# mackenziemillerschem1.net
KiCad netlist of a schematic drawn in Altium Designer
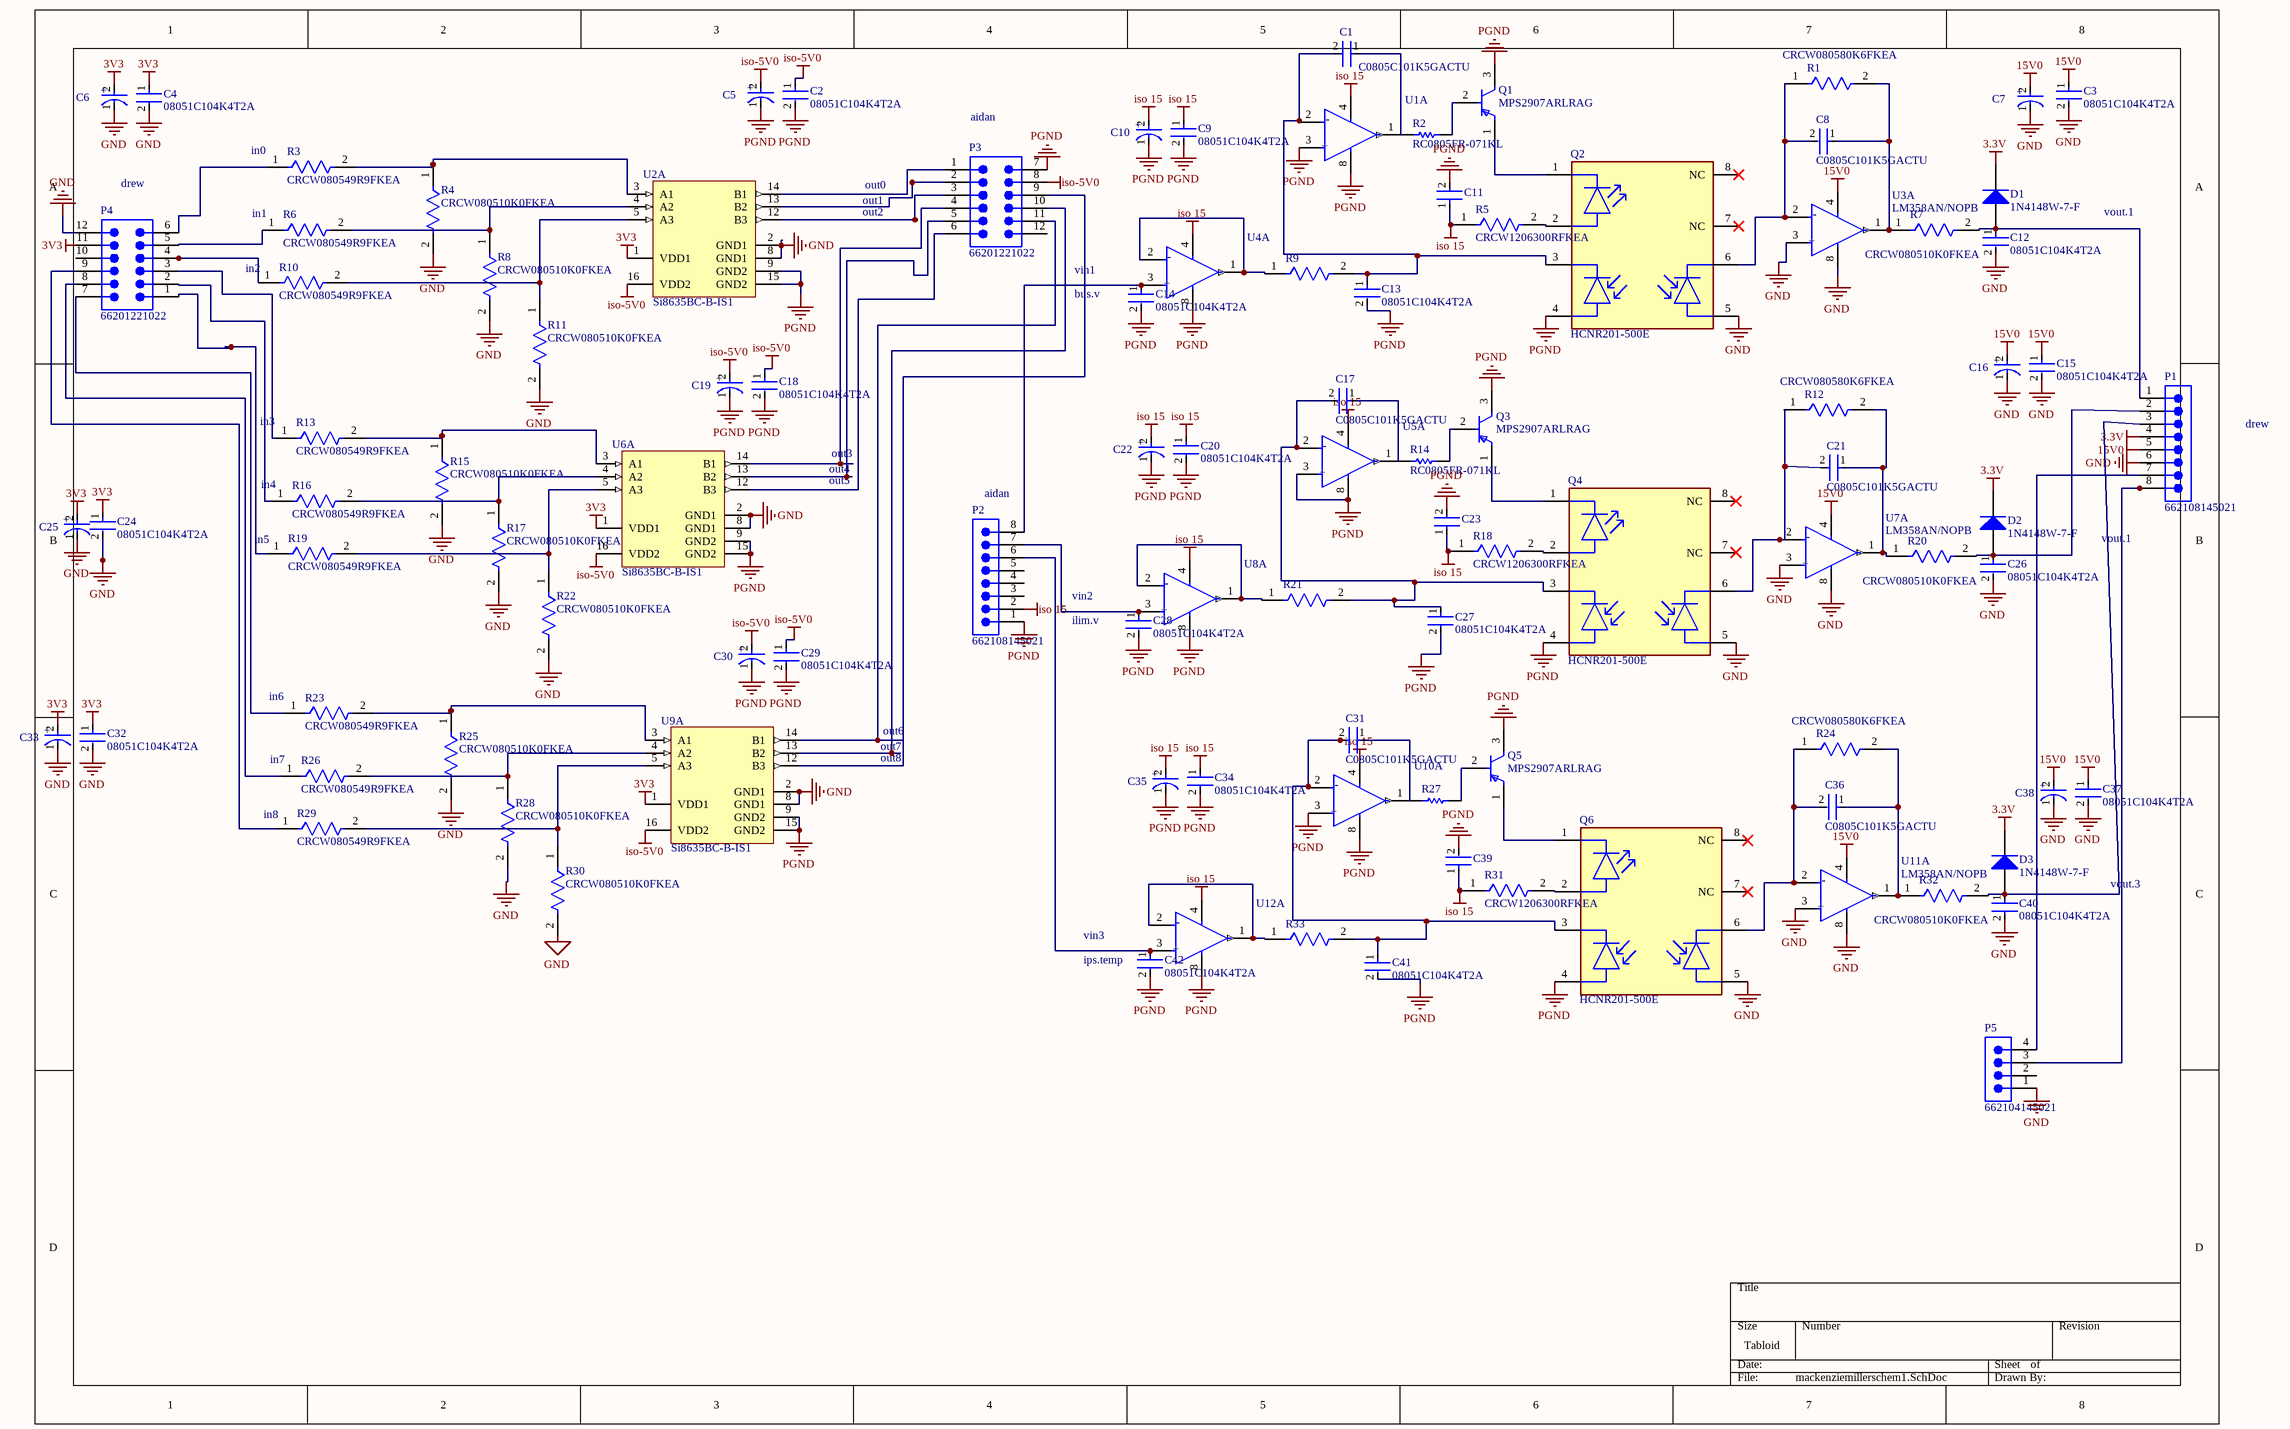
[diagram p0: mackenziemillerschem1.SchDoc]

(export (version "E")
  (design (tool "Eeschema 10.0.6"))
  (components
    (comp (ref "C1")
      (value "C0805C101K5GACTU")
      (footprint "FP-C0805C-DN-MFG")
      (description "CAP CER 100PF 50V C0G/NP0 0805")
      (fields
        (field (name "TOLERANCE") "0.1")
        (field (name "OCTOPART") "https://octopart.com/c0805c101k5gactu-kemet-109877")
      )
      (libsource (lib "Altium Content Vault") (part "b4654b650e69147ec39a6b967a45e02"))
    )
    (comp (ref "C2")
      (value "08051C104K4T2A")
      (footprint "FP-0805-L_2_01_0_2-W_1_25-IPC_B")
      (description "Automotive Ceramic Capacitor, 0805, 100nF, 10%, X7R, 15%, 100V")
      (fields (field (name "TOLERANCE") "10%") (field (name "VOLTAGE") "100V"))
      (libsource (lib "Altium Content Vault") (part "b4654b650e69147ec39a6b967a45e02"))
    )
    (comp (ref "C3")
      (value "08051C104K4T2A")
      (footprint "FP-0805-L_2_01_0_2-W_1_25-IPC_B")
      (description "Automotive Ceramic Capacitor, 0805, 100nF, 10%, X7R, 15%, 100V")
      (fields (field (name "TOLERANCE") "10%") (field (name "VOLTAGE") "100V"))
      (libsource (lib "Altium Content Vault") (part "b4654b650e69147ec39a6b967a45e02"))
    )
    (comp (ref "C4")
      (value "08051C104K4T2A")
      (footprint "FP-0805-L_2_01_0_2-W_1_25-IPC_B")
      (description "Automotive Ceramic Capacitor, 0805, 100nF, 10%, X7R, 15%, 100V")
      (fields (field (name "TOLERANCE") "10%") (field (name "VOLTAGE") "100V"))
      (libsource (lib "Altium Content Vault") (part "b4654b650e69147ec39a6b967a45e02"))
    )
    (comp (ref "C5")
      (value "293D106X9010B2TE3")
      (footprint "FP-293DB-MFG")
      (description "CAP TANT 10UF 10% 10V 1411")
      (fields (field (name "VOLTAGE") "10V") (field (name "TOLERANCE") "10%"))
      (libsource (lib "Altium Content Vault") (part "a00bbbee19879c290e62620ae7e47b1"))
    )
    (comp (ref "C6")
      (value "293D106X9010B2TE3")
      (footprint "FP-293DB-MFG")
      (description "CAP TANT 10UF 10% 10V 1411")
      (fields (field (name "VOLTAGE") "10V") (field (name "TOLERANCE") "10%"))
      (libsource (lib "Altium Content Vault") (part "a00bbbee19879c290e62620ae7e47b1"))
    )
    (comp (ref "C7")
      (value "293D106X9010B2TE3")
      (footprint "FP-293DB-MFG")
      (description "CAP TANT 10UF 10% 10V 1411")
      (fields (field (name "VOLTAGE") "10V") (field (name "TOLERANCE") "10%"))
      (libsource (lib "Altium Content Vault") (part "a00bbbee19879c290e62620ae7e47b1"))
    )
    (comp (ref "C8")
      (value "C0805C101K5GACTU")
      (footprint "FP-C0805C-DN-MFG")
      (description "CAP CER 100PF 50V C0G/NP0 0805")
      (fields
        (field (name "TOLERANCE") "0.1")
        (field (name "OCTOPART") "https://octopart.com/c0805c101k5gactu-kemet-109877")
      )
      (libsource (lib "Altium Content Vault") (part "b4654b650e69147ec39a6b967a45e02"))
    )
    (comp (ref "C9")
      (value "08051C104K4T2A")
      (footprint "FP-0805-L_2_01_0_2-W_1_25-IPC_B")
      (description "Automotive Ceramic Capacitor, 0805, 100nF, 10%, X7R, 15%, 100V")
      (fields (field (name "TOLERANCE") "10%") (field (name "VOLTAGE") "100V"))
      (libsource (lib "Altium Content Vault") (part "b4654b650e69147ec39a6b967a45e02"))
    )
    (comp (ref "C10")
      (value "293D106X9010B2TE3")
      (footprint "FP-293DB-MFG")
      (description "CAP TANT 10UF 10% 10V 1411")
      (fields (field (name "VOLTAGE") "10V") (field (name "TOLERANCE") "10%"))
      (libsource (lib "Altium Content Vault") (part "a00bbbee19879c290e62620ae7e47b1"))
    )
    (comp (ref "C11")
      (value "08051C104K4T2A")
      (footprint "FP-0805-L_2_01_0_2-W_1_25-IPC_B")
      (description "Automotive Ceramic Capacitor, 0805, 100nF, 10%, X7R, 15%, 100V")
      (fields (field (name "TOLERANCE") "10%") (field (name "VOLTAGE") "100V"))
      (libsource (lib "Altium Content Vault") (part "b4654b650e69147ec39a6b967a45e02"))
    )
    (comp (ref "C12")
      (value "08051C104K4T2A")
      (footprint "FP-0805-L_2_01_0_2-W_1_25-IPC_B")
      (description "Automotive Ceramic Capacitor, 0805, 100nF, 10%, X7R, 15%, 100V")
      (fields (field (name "TOLERANCE") "10%") (field (name "VOLTAGE") "100V"))
      (libsource (lib "Altium Content Vault") (part "b4654b650e69147ec39a6b967a45e02"))
    )
    (comp (ref "C13")
      (value "08051C104K4T2A")
      (footprint "FP-0805-L_2_01_0_2-W_1_25-IPC_B")
      (description "Automotive Ceramic Capacitor, 0805, 100nF, 10%, X7R, 15%, 100V")
      (fields (field (name "TOLERANCE") "10%") (field (name "VOLTAGE") "100V"))
      (libsource (lib "Altium Content Vault") (part "b4654b650e69147ec39a6b967a45e02"))
    )
    (comp (ref "C14")
      (value "08051C104K4T2A")
      (footprint "FP-0805-L_2_01_0_2-W_1_25-IPC_B")
      (description "Automotive Ceramic Capacitor, 0805, 100nF, 10%, X7R, 15%, 100V")
      (fields (field (name "TOLERANCE") "10%") (field (name "VOLTAGE") "100V"))
      (libsource (lib "Altium Content Vault") (part "b4654b650e69147ec39a6b967a45e02"))
    )
    (comp (ref "C15")
      (value "08051C104K4T2A")
      (footprint "FP-0805-L_2_01_0_2-W_1_25-IPC_B")
      (description "Automotive Ceramic Capacitor, 0805, 100nF, 10%, X7R, 15%, 100V")
      (fields (field (name "TOLERANCE") "10%") (field (name "VOLTAGE") "100V"))
      (libsource (lib "Altium Content Vault") (part "b4654b650e69147ec39a6b967a45e02"))
    )
    (comp (ref "C16")
      (value "293D106X9010B2TE3")
      (footprint "FP-293DB-MFG")
      (description "CAP TANT 10UF 10% 10V 1411")
      (fields (field (name "VOLTAGE") "10V") (field (name "TOLERANCE") "10%"))
      (libsource (lib "Altium Content Vault") (part "a00bbbee19879c290e62620ae7e47b1"))
    )
    (comp (ref "C17")
      (value "C0805C101K5GACTU")
      (footprint "FP-C0805C-DN-MFG")
      (description "CAP CER 100PF 50V C0G/NP0 0805")
      (fields
        (field (name "TOLERANCE") "0.1")
        (field (name "OCTOPART") "https://octopart.com/c0805c101k5gactu-kemet-109877")
      )
      (libsource (lib "Altium Content Vault") (part "b4654b650e69147ec39a6b967a45e02"))
    )
    (comp (ref "C18")
      (value "08051C104K4T2A")
      (footprint "FP-0805-L_2_01_0_2-W_1_25-IPC_B")
      (description "Automotive Ceramic Capacitor, 0805, 100nF, 10%, X7R, 15%, 100V")
      (fields (field (name "TOLERANCE") "10%") (field (name "VOLTAGE") "100V"))
      (libsource (lib "Altium Content Vault") (part "b4654b650e69147ec39a6b967a45e02"))
    )
    (comp (ref "C19")
      (value "293D106X9010B2TE3")
      (footprint "FP-293DB-MFG")
      (description "CAP TANT 10UF 10% 10V 1411")
      (fields (field (name "VOLTAGE") "10V") (field (name "TOLERANCE") "10%"))
      (libsource (lib "Altium Content Vault") (part "a00bbbee19879c290e62620ae7e47b1"))
    )
    (comp (ref "C20")
      (value "08051C104K4T2A")
      (footprint "FP-0805-L_2_01_0_2-W_1_25-IPC_B")
      (description "Automotive Ceramic Capacitor, 0805, 100nF, 10%, X7R, 15%, 100V")
      (fields (field (name "TOLERANCE") "10%") (field (name "VOLTAGE") "100V"))
      (libsource (lib "Altium Content Vault") (part "b4654b650e69147ec39a6b967a45e02"))
    )
    (comp (ref "C21")
      (value "C0805C101K5GACTU")
      (footprint "FP-C0805C-DN-MFG")
      (description "CAP CER 100PF 50V C0G/NP0 0805")
      (fields
        (field (name "TOLERANCE") "0.1")
        (field (name "OCTOPART") "https://octopart.com/c0805c101k5gactu-kemet-109877")
      )
      (libsource (lib "Altium Content Vault") (part "b4654b650e69147ec39a6b967a45e02"))
    )
    (comp (ref "C22")
      (value "293D106X9010B2TE3")
      (footprint "FP-293DB-MFG")
      (description "CAP TANT 10UF 10% 10V 1411")
      (fields (field (name "VOLTAGE") "10V") (field (name "TOLERANCE") "10%"))
      (libsource (lib "Altium Content Vault") (part "a00bbbee19879c290e62620ae7e47b1"))
    )
    (comp (ref "C23")
      (value "08051C104K4T2A")
      (footprint "FP-0805-L_2_01_0_2-W_1_25-IPC_B")
      (description "Automotive Ceramic Capacitor, 0805, 100nF, 10%, X7R, 15%, 100V")
      (fields (field (name "TOLERANCE") "10%") (field (name "VOLTAGE") "100V"))
      (libsource (lib "Altium Content Vault") (part "b4654b650e69147ec39a6b967a45e02"))
    )
    (comp (ref "C24")
      (value "08051C104K4T2A")
      (footprint "FP-0805-L_2_01_0_2-W_1_25-IPC_B")
      (description "Automotive Ceramic Capacitor, 0805, 100nF, 10%, X7R, 15%, 100V")
      (fields (field (name "TOLERANCE") "10%") (field (name "VOLTAGE") "100V"))
      (libsource (lib "Altium Content Vault") (part "b4654b650e69147ec39a6b967a45e02"))
    )
    (comp (ref "C25")
      (value "293D106X9010B2TE3")
      (footprint "FP-293DB-MFG")
      (description "CAP TANT 10UF 10% 10V 1411")
      (fields (field (name "VOLTAGE") "10V") (field (name "TOLERANCE") "10%"))
      (libsource (lib "Altium Content Vault") (part "a00bbbee19879c290e62620ae7e47b1"))
    )
    (comp (ref "C26")
      (value "08051C104K4T2A")
      (footprint "FP-0805-L_2_01_0_2-W_1_25-IPC_B")
      (description "Automotive Ceramic Capacitor, 0805, 100nF, 10%, X7R, 15%, 100V")
      (fields (field (name "TOLERANCE") "10%") (field (name "VOLTAGE") "100V"))
      (libsource (lib "Altium Content Vault") (part "b4654b650e69147ec39a6b967a45e02"))
    )
    (comp (ref "C27")
      (value "08051C104K4T2A")
      (footprint "FP-0805-L_2_01_0_2-W_1_25-IPC_B")
      (description "Automotive Ceramic Capacitor, 0805, 100nF, 10%, X7R, 15%, 100V")
      (fields (field (name "TOLERANCE") "10%") (field (name "VOLTAGE") "100V"))
      (libsource (lib "Altium Content Vault") (part "b4654b650e69147ec39a6b967a45e02"))
    )
    (comp (ref "C28")
      (value "08051C104K4T2A")
      (footprint "FP-0805-L_2_01_0_2-W_1_25-IPC_B")
      (description "Automotive Ceramic Capacitor, 0805, 100nF, 10%, X7R, 15%, 100V")
      (fields (field (name "TOLERANCE") "10%") (field (name "VOLTAGE") "100V"))
      (libsource (lib "Altium Content Vault") (part "b4654b650e69147ec39a6b967a45e02"))
    )
    (comp (ref "C29")
      (value "08051C104K4T2A")
      (footprint "FP-0805-L_2_01_0_2-W_1_25-IPC_B")
      (description "Automotive Ceramic Capacitor, 0805, 100nF, 10%, X7R, 15%, 100V")
      (fields (field (name "TOLERANCE") "10%") (field (name "VOLTAGE") "100V"))
      (libsource (lib "Altium Content Vault") (part "b4654b650e69147ec39a6b967a45e02"))
    )
    (comp (ref "C30")
      (value "293D106X9010B2TE3")
      (footprint "FP-293DB-MFG")
      (description "CAP TANT 10UF 10% 10V 1411")
      (fields (field (name "VOLTAGE") "10V") (field (name "TOLERANCE") "10%"))
      (libsource (lib "Altium Content Vault") (part "a00bbbee19879c290e62620ae7e47b1"))
    )
    (comp (ref "C31")
      (value "C0805C101K5GACTU")
      (footprint "FP-C0805C-DN-MFG")
      (description "CAP CER 100PF 50V C0G/NP0 0805")
      (fields
        (field (name "TOLERANCE") "0.1")
        (field (name "OCTOPART") "https://octopart.com/c0805c101k5gactu-kemet-109877")
      )
      (libsource (lib "Altium Content Vault") (part "b4654b650e69147ec39a6b967a45e02"))
    )
    (comp (ref "C32")
      (value "08051C104K4T2A")
      (footprint "FP-0805-L_2_01_0_2-W_1_25-IPC_B")
      (description "Automotive Ceramic Capacitor, 0805, 100nF, 10%, X7R, 15%, 100V")
      (fields (field (name "TOLERANCE") "10%") (field (name "VOLTAGE") "100V"))
      (libsource (lib "Altium Content Vault") (part "b4654b650e69147ec39a6b967a45e02"))
    )
    (comp (ref "C33")
      (value "293D106X9010B2TE3")
      (footprint "FP-293DB-MFG")
      (description "CAP TANT 10UF 10% 10V 1411")
      (fields (field (name "VOLTAGE") "10V") (field (name "TOLERANCE") "10%"))
      (libsource (lib "Altium Content Vault") (part "a00bbbee19879c290e62620ae7e47b1"))
    )
    (comp (ref "C34")
      (value "08051C104K4T2A")
      (footprint "FP-0805-L_2_01_0_2-W_1_25-IPC_B")
      (description "Automotive Ceramic Capacitor, 0805, 100nF, 10%, X7R, 15%, 100V")
      (fields (field (name "TOLERANCE") "10%") (field (name "VOLTAGE") "100V"))
      (libsource (lib "Altium Content Vault") (part "b4654b650e69147ec39a6b967a45e02"))
    )
    (comp (ref "C35")
      (value "293D106X9010B2TE3")
      (footprint "FP-293DB-MFG")
      (description "CAP TANT 10UF 10% 10V 1411")
      (fields (field (name "VOLTAGE") "10V") (field (name "TOLERANCE") "10%"))
      (libsource (lib "Altium Content Vault") (part "a00bbbee19879c290e62620ae7e47b1"))
    )
    (comp (ref "C36")
      (value "C0805C101K5GACTU")
      (footprint "FP-C0805C-DN-MFG")
      (description "CAP CER 100PF 50V C0G/NP0 0805")
      (fields
        (field (name "TOLERANCE") "0.1")
        (field (name "OCTOPART") "https://octopart.com/c0805c101k5gactu-kemet-109877")
      )
      (libsource (lib "Altium Content Vault") (part "b4654b650e69147ec39a6b967a45e02"))
    )
    (comp (ref "C37")
      (value "08051C104K4T2A")
      (footprint "FP-0805-L_2_01_0_2-W_1_25-IPC_B")
      (description "Automotive Ceramic Capacitor, 0805, 100nF, 10%, X7R, 15%, 100V")
      (fields (field (name "TOLERANCE") "10%") (field (name "VOLTAGE") "100V"))
      (libsource (lib "Altium Content Vault") (part "b4654b650e69147ec39a6b967a45e02"))
    )
    (comp (ref "C38")
      (value "293D106X9010B2TE3")
      (footprint "FP-293DB-MFG")
      (description "CAP TANT 10UF 10% 10V 1411")
      (fields (field (name "VOLTAGE") "10V") (field (name "TOLERANCE") "10%"))
      (libsource (lib "Altium Content Vault") (part "a00bbbee19879c290e62620ae7e47b1"))
    )
    (comp (ref "C39")
      (value "08051C104K4T2A")
      (footprint "FP-0805-L_2_01_0_2-W_1_25-IPC_B")
      (description "Automotive Ceramic Capacitor, 0805, 100nF, 10%, X7R, 15%, 100V")
      (fields (field (name "TOLERANCE") "10%") (field (name "VOLTAGE") "100V"))
      (libsource (lib "Altium Content Vault") (part "b4654b650e69147ec39a6b967a45e02"))
    )
    (comp (ref "C40")
      (value "08051C104K4T2A")
      (footprint "FP-0805-L_2_01_0_2-W_1_25-IPC_B")
      (description "Automotive Ceramic Capacitor, 0805, 100nF, 10%, X7R, 15%, 100V")
      (fields (field (name "TOLERANCE") "10%") (field (name "VOLTAGE") "100V"))
      (libsource (lib "Altium Content Vault") (part "b4654b650e69147ec39a6b967a45e02"))
    )
    (comp (ref "C41")
      (value "08051C104K4T2A")
      (footprint "FP-0805-L_2_01_0_2-W_1_25-IPC_B")
      (description "Automotive Ceramic Capacitor, 0805, 100nF, 10%, X7R, 15%, 100V")
      (fields (field (name "TOLERANCE") "10%") (field (name "VOLTAGE") "100V"))
      (libsource (lib "Altium Content Vault") (part "b4654b650e69147ec39a6b967a45e02"))
    )
    (comp (ref "C42")
      (value "08051C104K4T2A")
      (footprint "FP-0805-L_2_01_0_2-W_1_25-IPC_B")
      (description "Automotive Ceramic Capacitor, 0805, 100nF, 10%, X7R, 15%, 100V")
      (fields (field (name "TOLERANCE") "10%") (field (name "VOLTAGE") "100V"))
      (libsource (lib "Altium Content Vault") (part "b4654b650e69147ec39a6b967a45e02"))
    )
    (comp (ref "D1")
      (value "1N4148W-7-F")
      (footprint "DIOD-SOD123-2_V")
      (description "Fast Switching Diode, 100 V, 0.15 A, -65 to 150 degC, 2-Pin?SOD123, RoHS, Tape and Reel")
      (fields (field (name "MANUFACTURER") "DiodesIncorporated"))
      (libsource (lib "Altium Content Vault") (part "D-AK-2"))
    )
    (comp (ref "D2")
      (value "1N4148W-7-F")
      (footprint "DIOD-SOD123-2_V")
      (description "Fast Switching Diode, 100 V, 0.15 A, -65 to 150 degC, 2-Pin?SOD123, RoHS, Tape and Reel")
      (fields (field (name "MANUFACTURER") "DiodesIncorporated"))
      (libsource (lib "Altium Content Vault") (part "D-AK-2"))
    )
    (comp (ref "D3")
      (value "1N4148W-7-F")
      (footprint "DIOD-SOD123-2_V")
      (description "Fast Switching Diode, 100 V, 0.15 A, -65 to 150 degC, 2-Pin?SOD123, RoHS, Tape and Reel")
      (fields (field (name "MANUFACTURER") "DiodesIncorporated"))
      (libsource (lib "Altium Content Vault") (part "D-AK-2"))
    )
    (comp (ref "P1")
      (value "662108145021")
      (footprint "662108145021")
      (libsource (lib "Altium Content Vault") (part "Header_Male_1R_08P"))
    )
    (comp (ref "P2")
      (value "662108145021")
      (footprint "662108145021")
      (libsource (lib "Altium Content Vault") (part "Header_Male_1R_08P"))
    )
    (comp (ref "P3")
      (value "66201221022")
      (footprint "66201221022")
      (libsource (lib "Altium Content Vault") (part "Header_Male_2R_12P(A)"))
    )
    (comp (ref "P4")
      (value "66201221022")
      (footprint "66201221022")
      (libsource (lib "Altium Content Vault") (part "Header_Male_2R_12P(A)"))
    )
    (comp (ref "P5")
      (value "662104145021")
      (footprint "662104145021")
      (libsource (lib "Altium Content Vault") (part "Header_Male_1R_04P"))
    )
    (comp (ref "Q1")
      (value "MPS2907ARLRAG")
      (footprint "FP-29-11-MFG")
      (libsource (lib "Altium Content Vault") (part "43163f20067017cd0425b43859cd0db"))
    )
    (comp (ref "Q2")
      (value "HCNR201-500E")
      (footprint "FP-HCNR201-500E-MFG")
      (description "OPTOISO 5KV LINEAR PHVOLT 8DIPGW")
      (libsource (lib "Altium Content Vault") (part "91ab35065b22d0708acdc738a14b8cf"))
    )
    (comp (ref "Q3")
      (value "MPS2907ARLRAG")
      (footprint "FP-29-11-MFG")
      (libsource (lib "Altium Content Vault") (part "43163f20067017cd0425b43859cd0db"))
    )
    (comp (ref "Q4")
      (value "HCNR201-500E")
      (footprint "FP-HCNR201-500E-MFG")
      (description "OPTOISO 5KV LINEAR PHVOLT 8DIPGW")
      (libsource (lib "Altium Content Vault") (part "91ab35065b22d0708acdc738a14b8cf"))
    )
    (comp (ref "Q5")
      (value "MPS2907ARLRAG")
      (footprint "FP-29-11-MFG")
      (libsource (lib "Altium Content Vault") (part "43163f20067017cd0425b43859cd0db"))
    )
    (comp (ref "Q6")
      (value "HCNR201-500E")
      (footprint "FP-HCNR201-500E-MFG")
      (description "OPTOISO 5KV LINEAR PHVOLT 8DIPGW")
      (libsource (lib "Altium Content Vault") (part "91ab35065b22d0708acdc738a14b8cf"))
    )
    (comp (ref "R1")
      (value "CRCW080580K6FKEA")
      (footprint "FP-CRCW0805-e3-IPC_A")
      (description "RES Thick Film, 80.6kΩ, 1%, 0.125W, 100ppm/°C, 0805")
      (fields (field (name "TOLERANCE") "1%"))
      (libsource (lib "Altium Content Vault") (part "1029c3af85768c4190bb7ad29bc67b5"))
    )
    (comp (ref "R2")
      (value "RC0805FR-071KL")
      (footprint "RESC2013X60X35ML10T20")
      (description "Chip Resistor, 1 KOhm, +/- 1%, 125 mW, -55 to 155 degC, 0805 (2012 Metric), RoHS, Tape and Reel")
      (fields (field (name "TOLERANCE") "1%") (field (name "MANUFACTURER") "Yageo"))
      (libsource (lib "Altium Content Vault") (part "RES-2"))
    )
    (comp (ref "R3")
      (value "CRCW080549R9FKEA")
      (footprint "FP-CRCW0805-e3-MFG")
      (description "RES Thick Film, 49.9Ω, 1%, 0.125W, 100ppm/°C, 0805")
      (fields (field (name "TOLERANCE") "1%"))
      (libsource (lib "Altium Content Vault") (part "1029c3af85768c4190bb7ad29bc67b5"))
    )
    (comp (ref "R4")
      (value "CRCW080510K0FKEA")
      (footprint "FP-CRCW0805-e3-IPC_A")
      (description "RES Thick Film, 10kΩ, 1%, 0.125W, 100ppm/°C, 0805")
      (fields (field (name "TOLERANCE") "1%"))
      (libsource (lib "Altium Content Vault") (part "1029c3af85768c4190bb7ad29bc67b5"))
    )
    (comp (ref "R5")
      (value "CRCW1206300RFKEA")
      (footprint "FP-CRCW1206-e3-IPC_A")
      (description "RES Thick Film, 300Ω, 1%, 0.25W, 100ppm/°C, 1206")
      (fields (field (name "TOLERANCE") "1%"))
      (libsource (lib "Altium Content Vault") (part "1029c3af85768c4190bb7ad29bc67b5"))
    )
    (comp (ref "R6")
      (value "CRCW080549R9FKEA")
      (footprint "FP-CRCW0805-e3-MFG")
      (description "RES Thick Film, 49.9Ω, 1%, 0.125W, 100ppm/°C, 0805")
      (fields (field (name "TOLERANCE") "1%"))
      (libsource (lib "Altium Content Vault") (part "1029c3af85768c4190bb7ad29bc67b5"))
    )
    (comp (ref "R7")
      (value "CRCW080510K0FKEA")
      (footprint "FP-CRCW0805-e3-IPC_A")
      (description "RES Thick Film, 10kΩ, 1%, 0.125W, 100ppm/°C, 0805")
      (fields (field (name "TOLERANCE") "1%"))
      (libsource (lib "Altium Content Vault") (part "1029c3af85768c4190bb7ad29bc67b5"))
    )
    (comp (ref "R8")
      (value "CRCW080510K0FKEA")
      (footprint "FP-CRCW0805-e3-IPC_A")
      (description "RES Thick Film, 10kΩ, 1%, 0.125W, 100ppm/°C, 0805")
      (fields (field (name "TOLERANCE") "1%"))
      (libsource (lib "Altium Content Vault") (part "1029c3af85768c4190bb7ad29bc67b5"))
    )
    (comp (ref "R9")
      (value "CRCW080580K6FKEA")
      (footprint "FP-CRCW0805-e3-IPC_A")
      (description "RES Thick Film, 80.6kΩ, 1%, 0.125W, 100ppm/°C, 0805")
      (fields (field (name "TOLERANCE") "1%"))
      (libsource (lib "Altium Content Vault") (part "1029c3af85768c4190bb7ad29bc67b5"))
    )
    (comp (ref "R10")
      (value "CRCW080549R9FKEA")
      (footprint "FP-CRCW0805-e3-MFG")
      (description "RES Thick Film, 49.9Ω, 1%, 0.125W, 100ppm/°C, 0805")
      (fields (field (name "TOLERANCE") "1%"))
      (libsource (lib "Altium Content Vault") (part "1029c3af85768c4190bb7ad29bc67b5"))
    )
    (comp (ref "R11")
      (value "CRCW080510K0FKEA")
      (footprint "FP-CRCW0805-e3-IPC_A")
      (description "RES Thick Film, 10kΩ, 1%, 0.125W, 100ppm/°C, 0805")
      (fields (field (name "TOLERANCE") "1%"))
      (libsource (lib "Altium Content Vault") (part "1029c3af85768c4190bb7ad29bc67b5"))
    )
    (comp (ref "R12")
      (value "CRCW080580K6FKEA")
      (footprint "FP-CRCW0805-e3-IPC_A")
      (description "RES Thick Film, 80.6kΩ, 1%, 0.125W, 100ppm/°C, 0805")
      (fields (field (name "TOLERANCE") "1%"))
      (libsource (lib "Altium Content Vault") (part "1029c3af85768c4190bb7ad29bc67b5"))
    )
    (comp (ref "R13")
      (value "CRCW080549R9FKEA")
      (footprint "FP-CRCW0805-e3-MFG")
      (description "RES Thick Film, 49.9Ω, 1%, 0.125W, 100ppm/°C, 0805")
      (fields (field (name "TOLERANCE") "1%"))
      (libsource (lib "Altium Content Vault") (part "1029c3af85768c4190bb7ad29bc67b5"))
    )
    (comp (ref "R14")
      (value "RC0805FR-071KL")
      (footprint "RESC2013X60X35ML10T20")
      (description "Chip Resistor, 1 KOhm, +/- 1%, 125 mW, -55 to 155 degC, 0805 (2012 Metric), RoHS, Tape and Reel")
      (fields (field (name "TOLERANCE") "1%") (field (name "MANUFACTURER") "Yageo"))
      (libsource (lib "Altium Content Vault") (part "RES-2"))
    )
    (comp (ref "R15")
      (value "CRCW080510K0FKEA")
      (footprint "FP-CRCW0805-e3-IPC_A")
      (description "RES Thick Film, 10kΩ, 1%, 0.125W, 100ppm/°C, 0805")
      (fields (field (name "TOLERANCE") "1%"))
      (libsource (lib "Altium Content Vault") (part "1029c3af85768c4190bb7ad29bc67b5"))
    )
    (comp (ref "R16")
      (value "CRCW080549R9FKEA")
      (footprint "FP-CRCW0805-e3-MFG")
      (description "RES Thick Film, 49.9Ω, 1%, 0.125W, 100ppm/°C, 0805")
      (fields (field (name "TOLERANCE") "1%"))
      (libsource (lib "Altium Content Vault") (part "1029c3af85768c4190bb7ad29bc67b5"))
    )
    (comp (ref "R17")
      (value "CRCW080510K0FKEA")
      (footprint "FP-CRCW0805-e3-IPC_A")
      (description "RES Thick Film, 10kΩ, 1%, 0.125W, 100ppm/°C, 0805")
      (fields (field (name "TOLERANCE") "1%"))
      (libsource (lib "Altium Content Vault") (part "1029c3af85768c4190bb7ad29bc67b5"))
    )
    (comp (ref "R18")
      (value "CRCW1206300RFKEA")
      (footprint "FP-CRCW1206-e3-IPC_A")
      (description "RES Thick Film, 300Ω, 1%, 0.25W, 100ppm/°C, 1206")
      (fields (field (name "TOLERANCE") "1%"))
      (libsource (lib "Altium Content Vault") (part "1029c3af85768c4190bb7ad29bc67b5"))
    )
    (comp (ref "R19")
      (value "CRCW080549R9FKEA")
      (footprint "FP-CRCW0805-e3-MFG")
      (description "RES Thick Film, 49.9Ω, 1%, 0.125W, 100ppm/°C, 0805")
      (fields (field (name "TOLERANCE") "1%"))
      (libsource (lib "Altium Content Vault") (part "1029c3af85768c4190bb7ad29bc67b5"))
    )
    (comp (ref "R20")
      (value "CRCW080510K0FKEA")
      (footprint "FP-CRCW0805-e3-IPC_A")
      (description "RES Thick Film, 10kΩ, 1%, 0.125W, 100ppm/°C, 0805")
      (fields (field (name "TOLERANCE") "1%"))
      (libsource (lib "Altium Content Vault") (part "1029c3af85768c4190bb7ad29bc67b5"))
    )
    (comp (ref "R21")
      (value "CRCW080580K6FKEA")
      (footprint "FP-CRCW0805-e3-IPC_A")
      (description "RES Thick Film, 80.6kΩ, 1%, 0.125W, 100ppm/°C, 0805")
      (fields (field (name "TOLERANCE") "1%"))
      (libsource (lib "Altium Content Vault") (part "1029c3af85768c4190bb7ad29bc67b5"))
    )
    (comp (ref "R22")
      (value "CRCW080510K0FKEA")
      (footprint "FP-CRCW0805-e3-IPC_A")
      (description "RES Thick Film, 10kΩ, 1%, 0.125W, 100ppm/°C, 0805")
      (fields (field (name "TOLERANCE") "1%"))
      (libsource (lib "Altium Content Vault") (part "1029c3af85768c4190bb7ad29bc67b5"))
    )
    (comp (ref "R23")
      (value "CRCW080549R9FKEA")
      (footprint "FP-CRCW0805-e3-MFG")
      (description "RES Thick Film, 49.9Ω, 1%, 0.125W, 100ppm/°C, 0805")
      (fields (field (name "TOLERANCE") "1%"))
      (libsource (lib "Altium Content Vault") (part "1029c3af85768c4190bb7ad29bc67b5"))
    )
    (comp (ref "R24")
      (value "CRCW080580K6FKEA")
      (footprint "FP-CRCW0805-e3-IPC_A")
      (description "RES Thick Film, 80.6kΩ, 1%, 0.125W, 100ppm/°C, 0805")
      (fields (field (name "TOLERANCE") "1%"))
      (libsource (lib "Altium Content Vault") (part "1029c3af85768c4190bb7ad29bc67b5"))
    )
    (comp (ref "R25")
      (value "CRCW080510K0FKEA")
      (footprint "FP-CRCW0805-e3-IPC_A")
      (description "RES Thick Film, 10kΩ, 1%, 0.125W, 100ppm/°C, 0805")
      (fields (field (name "TOLERANCE") "1%"))
      (libsource (lib "Altium Content Vault") (part "1029c3af85768c4190bb7ad29bc67b5"))
    )
    (comp (ref "R26")
      (value "CRCW080549R9FKEA")
      (footprint "FP-CRCW0805-e3-MFG")
      (description "RES Thick Film, 49.9Ω, 1%, 0.125W, 100ppm/°C, 0805")
      (fields (field (name "TOLERANCE") "1%"))
      (libsource (lib "Altium Content Vault") (part "1029c3af85768c4190bb7ad29bc67b5"))
    )
    (comp (ref "R27")
      (value "RC0805FR-071KL")
      (footprint "RESC2013X60X35ML10T20")
      (description "Chip Resistor, 1 KOhm, +/- 1%, 125 mW, -55 to 155 degC, 0805 (2012 Metric), RoHS, Tape and Reel")
      (fields (field (name "TOLERANCE") "1%") (field (name "MANUFACTURER") "Yageo"))
      (libsource (lib "Altium Content Vault") (part "RES-2"))
    )
    (comp (ref "R28")
      (value "CRCW080510K0FKEA")
      (footprint "FP-CRCW0805-e3-IPC_A")
      (description "RES Thick Film, 10kΩ, 1%, 0.125W, 100ppm/°C, 0805")
      (fields (field (name "TOLERANCE") "1%"))
      (libsource (lib "Altium Content Vault") (part "1029c3af85768c4190bb7ad29bc67b5"))
    )
    (comp (ref "R29")
      (value "CRCW080549R9FKEA")
      (footprint "FP-CRCW0805-e3-MFG")
      (description "RES Thick Film, 49.9Ω, 1%, 0.125W, 100ppm/°C, 0805")
      (fields (field (name "TOLERANCE") "1%"))
      (libsource (lib "Altium Content Vault") (part "1029c3af85768c4190bb7ad29bc67b5"))
    )
    (comp (ref "R30")
      (value "CRCW080510K0FKEA")
      (footprint "FP-CRCW0805-e3-IPC_A")
      (description "RES Thick Film, 10kΩ, 1%, 0.125W, 100ppm/°C, 0805")
      (fields (field (name "TOLERANCE") "1%"))
      (libsource (lib "Altium Content Vault") (part "1029c3af85768c4190bb7ad29bc67b5"))
    )
    (comp (ref "R31")
      (value "CRCW1206300RFKEA")
      (footprint "FP-CRCW1206-e3-IPC_A")
      (description "RES Thick Film, 300Ω, 1%, 0.25W, 100ppm/°C, 1206")
      (fields (field (name "TOLERANCE") "1%"))
      (libsource (lib "Altium Content Vault") (part "1029c3af85768c4190bb7ad29bc67b5"))
    )
    (comp (ref "R32")
      (value "CRCW080510K0FKEA")
      (footprint "FP-CRCW0805-e3-IPC_A")
      (description "RES Thick Film, 10kΩ, 1%, 0.125W, 100ppm/°C, 0805")
      (fields (field (name "TOLERANCE") "1%"))
      (libsource (lib "Altium Content Vault") (part "1029c3af85768c4190bb7ad29bc67b5"))
    )
    (comp (ref "R33")
      (value "CRCW080580K6FKEA")
      (footprint "FP-CRCW0805-e3-IPC_A")
      (description "RES Thick Film, 80.6kΩ, 1%, 0.125W, 100ppm/°C, 0805")
      (fields (field (name "TOLERANCE") "1%"))
      (libsource (lib "Altium Content Vault") (part "1029c3af85768c4190bb7ad29bc67b5"))
    )
    (comp (ref "U1")
      (value "LM358AN/NOPB")
      (footprint "FP-P0008A-MFG")
      (description "IC OPAMP GP 2 CIRCUIT 8DIP")
      (fields
        (field (name "MANUFACTURER") "Texas Instruments")
        (field (name "OCTOPART") "https://octopart.com/lm358an%2Fnopb-texas+instruments-24814014")
      )
      (libsource (lib "Altium Content Vault") (part "1d8c551adc971fa6d54955cbfc8f220"))
    )
    (comp (ref "U2")
      (value "Si8635BC-B-IS1")
      (footprint "SLAB-SOIC-16-NB_L")
      (fields (field (name "MANUFACTURER") "Silicon Labs"))
      (libsource (lib "Altium Content Vault") (part "SLAB-Si8435BB-SOIC-16-XB-16"))
    )
    (comp (ref "U3")
      (value "LM358AN/NOPB")
      (footprint "FP-P0008A-MFG")
      (description "IC OPAMP GP 2 CIRCUIT 8DIP")
      (fields
        (field (name "MANUFACTURER") "Texas Instruments")
        (field (name "OCTOPART") "https://octopart.com/lm358an%2Fnopb-texas+instruments-24814014")
      )
      (libsource (lib "Altium Content Vault") (part "1d8c551adc971fa6d54955cbfc8f220"))
    )
    (comp (ref "U4")
      (value "LM358AN/NOPB")
      (footprint "FP-P0008A-MFG")
      (description "IC OPAMP GP 2 CIRCUIT 8DIP")
      (fields
        (field (name "MANUFACTURER") "Texas Instruments")
        (field (name "OCTOPART") "https://octopart.com/lm358an%2Fnopb-texas+instruments-24814014")
      )
      (libsource (lib "Altium Content Vault") (part "1d8c551adc971fa6d54955cbfc8f220"))
    )
    (comp (ref "U5")
      (value "LM358AN/NOPB")
      (footprint "FP-P0008A-MFG")
      (description "IC OPAMP GP 2 CIRCUIT 8DIP")
      (fields
        (field (name "MANUFACTURER") "Texas Instruments")
        (field (name "OCTOPART") "https://octopart.com/lm358an%2Fnopb-texas+instruments-24814014")
      )
      (libsource (lib "Altium Content Vault") (part "1d8c551adc971fa6d54955cbfc8f220"))
    )
    (comp (ref "U6")
      (value "Si8635BC-B-IS1")
      (footprint "SLAB-SOIC-16-NB_L")
      (fields (field (name "MANUFACTURER") "Silicon Labs"))
      (libsource (lib "Altium Content Vault") (part "SLAB-Si8435BB-SOIC-16-XB-16"))
    )
    (comp (ref "U7")
      (value "LM358AN/NOPB")
      (footprint "FP-P0008A-MFG")
      (description "IC OPAMP GP 2 CIRCUIT 8DIP")
      (fields
        (field (name "MANUFACTURER") "Texas Instruments")
        (field (name "OCTOPART") "https://octopart.com/lm358an%2Fnopb-texas+instruments-24814014")
      )
      (libsource (lib "Altium Content Vault") (part "1d8c551adc971fa6d54955cbfc8f220"))
    )
    (comp (ref "U8")
      (value "LM358AN/NOPB")
      (footprint "FP-P0008A-MFG")
      (description "IC OPAMP GP 2 CIRCUIT 8DIP")
      (fields
        (field (name "MANUFACTURER") "Texas Instruments")
        (field (name "OCTOPART") "https://octopart.com/lm358an%2Fnopb-texas+instruments-24814014")
      )
      (libsource (lib "Altium Content Vault") (part "1d8c551adc971fa6d54955cbfc8f220"))
    )
    (comp (ref "U9")
      (value "Si8635BC-B-IS1")
      (footprint "SLAB-SOIC-16-NB_L")
      (fields (field (name "MANUFACTURER") "Silicon Labs"))
      (libsource (lib "Altium Content Vault") (part "SLAB-Si8435BB-SOIC-16-XB-16"))
    )
    (comp (ref "U10")
      (value "LM358AN/NOPB")
      (footprint "FP-P0008A-MFG")
      (description "IC OPAMP GP 2 CIRCUIT 8DIP")
      (fields
        (field (name "MANUFACTURER") "Texas Instruments")
        (field (name "OCTOPART") "https://octopart.com/lm358an%2Fnopb-texas+instruments-24814014")
      )
      (libsource (lib "Altium Content Vault") (part "1d8c551adc971fa6d54955cbfc8f220"))
    )
    (comp (ref "U11")
      (value "LM358AN/NOPB")
      (footprint "FP-P0008A-MFG")
      (description "IC OPAMP GP 2 CIRCUIT 8DIP")
      (fields
        (field (name "MANUFACTURER") "Texas Instruments")
        (field (name "OCTOPART") "https://octopart.com/lm358an%2Fnopb-texas+instruments-24814014")
      )
      (libsource (lib "Altium Content Vault") (part "1d8c551adc971fa6d54955cbfc8f220"))
    )
    (comp (ref "U12")
      (value "LM358AN/NOPB")
      (footprint "FP-P0008A-MFG")
      (description "IC OPAMP GP 2 CIRCUIT 8DIP")
      (fields
        (field (name "MANUFACTURER") "Texas Instruments")
        (field (name "OCTOPART") "https://octopart.com/lm358an%2Fnopb-texas+instruments-24814014")
      )
      (libsource (lib "Altium Content Vault") (part "1d8c551adc971fa6d54955cbfc8f220"))
    )
  )
  (nets
    (net (code "1") (name "3.3V") (class "Default")
      (node (ref "D1") (pin "2") (pinfunction "K_2") (pintype "passive"))
      (node (ref "D2") (pin "2") (pinfunction "K_2") (pintype "passive"))
      (node (ref "D3") (pin "2") (pinfunction "K_2") (pintype "passive"))
      (node (ref "P1") (pin "4") (pinfunction "4_4") (pintype "passive"))
    )
    (net (code "2") (name "3V3") (class "Default")
      (node (ref "C24") (pin "1") (pinfunction "1_1") (pintype "passive"))
      (node (ref "C25") (pin "2") (pinfunction "A_2") (pintype "passive"))
      (node (ref "C32") (pin "1") (pinfunction "1_1") (pintype "passive"))
      (node (ref "C33") (pin "2") (pinfunction "A_2") (pintype "passive"))
      (node (ref "C4") (pin "1") (pinfunction "1_1") (pintype "passive"))
      (node (ref "C6") (pin "2") (pinfunction "A_2") (pintype "passive"))
      (node (ref "U2") (pin "1") (pinfunction "VDD1_1") (pintype "power_in"))
      (node (ref "U6") (pin "1") (pinfunction "VDD1_1") (pintype "power_in"))
      (node (ref "U9") (pin "1") (pinfunction "VDD1_1") (pintype "power_in"))
    )
    (net (code "3") (name "15V0") (class "Default")
      (node (ref "C15") (pin "1") (pinfunction "1_1") (pintype "passive"))
      (node (ref "C16") (pin "2") (pinfunction "A_2") (pintype "passive"))
      (node (ref "C3") (pin "1") (pinfunction "1_1") (pintype "passive"))
      (node (ref "C37") (pin "1") (pinfunction "1_1") (pintype "passive"))
      (node (ref "C38") (pin "2") (pinfunction "A_2") (pintype "passive"))
      (node (ref "C7") (pin "2") (pinfunction "A_2") (pintype "passive"))
      (node (ref "P1") (pin "5") (pinfunction "5_5") (pintype "passive"))
      (node (ref "U11") (pin "4") (pinfunction "GND_4") (pintype "power_in"))
      (node (ref "U3") (pin "4") (pinfunction "GND_4") (pintype "power_in"))
      (node (ref "U7") (pin "4") (pinfunction "GND_4") (pintype "power_in"))
    )
    (net (code "4") (name "GND") (class "Default")
      (node (ref "C12") (pin "2") (pinfunction "2_2") (pintype "passive"))
      (node (ref "C15") (pin "2") (pinfunction "2_2") (pintype "passive"))
      (node (ref "C16") (pin "1") (pinfunction "C_1") (pintype "passive"))
      (node (ref "C24") (pin "2") (pinfunction "2_2") (pintype "passive"))
      (node (ref "C25") (pin "1") (pinfunction "C_1") (pintype "passive"))
      (node (ref "C26") (pin "2") (pinfunction "2_2") (pintype "passive"))
      (node (ref "C3") (pin "2") (pinfunction "2_2") (pintype "passive"))
      (node (ref "C32") (pin "2") (pinfunction "2_2") (pintype "passive"))
      (node (ref "C33") (pin "1") (pinfunction "C_1") (pintype "passive"))
      (node (ref "C37") (pin "2") (pinfunction "2_2") (pintype "passive"))
      (node (ref "C38") (pin "1") (pinfunction "C_1") (pintype "passive"))
      (node (ref "C4") (pin "2") (pinfunction "2_2") (pintype "passive"))
      (node (ref "C40") (pin "2") (pinfunction "2_2") (pintype "passive"))
      (node (ref "C6") (pin "1") (pinfunction "C_1") (pintype "passive"))
      (node (ref "C7") (pin "1") (pinfunction "C_1") (pintype "passive"))
      (node (ref "P1") (pin "6") (pinfunction "6_6") (pintype "passive"))
      (node (ref "P4") (pin "12") (pinfunction "12_12") (pintype "passive"))
      (node (ref "P5") (pin "1") (pinfunction "1_1") (pintype "passive"))
      (node (ref "Q2") (pin "5") (pinfunction "PD2_ANODE_5") (pintype "passive"))
      (node (ref "Q4") (pin "5") (pinfunction "PD2_ANODE_5") (pintype "passive"))
      (node (ref "Q6") (pin "5") (pinfunction "PD2_ANODE_5") (pintype "passive"))
      (node (ref "R11") (pin "2") (pinfunction "2_2") (pintype "passive"))
      (node (ref "R15") (pin "2") (pinfunction "2_2") (pintype "passive"))
      (node (ref "R17") (pin "2") (pinfunction "2_2") (pintype "passive"))
      (node (ref "R22") (pin "2") (pinfunction "2_2") (pintype "passive"))
      (node (ref "R25") (pin "2") (pinfunction "2_2") (pintype "passive"))
      (node (ref "R28") (pin "2") (pinfunction "2_2") (pintype "passive"))
      (node (ref "R30") (pin "2") (pinfunction "2_2") (pintype "passive"))
      (node (ref "R4") (pin "2") (pinfunction "2_2") (pintype "passive"))
      (node (ref "R8") (pin "2") (pinfunction "2_2") (pintype "passive"))
      (node (ref "U11") (pin "3") (pinfunction "NON-INVERTING_INPUT_A_3") (pintype "tri_state"))
      (node (ref "U11") (pin "8") (pinfunction "V+_8") (pintype "power_in"))
      (node (ref "U2") (pin "2") (pinfunction "GND1_2") (pintype "power_in"))
      (node (ref "U2") (pin "8") (pinfunction "GND1_8") (pintype "power_in"))
      (node (ref "U3") (pin "3") (pinfunction "NON-INVERTING_INPUT_A_3") (pintype "tri_state"))
      (node (ref "U3") (pin "8") (pinfunction "V+_8") (pintype "power_in"))
      (node (ref "U6") (pin "2") (pinfunction "GND1_2") (pintype "power_in"))
      (node (ref "U6") (pin "8") (pinfunction "GND1_8") (pintype "power_in"))
      (node (ref "U7") (pin "3") (pinfunction "NON-INVERTING_INPUT_A_3") (pintype "tri_state"))
      (node (ref "U7") (pin "8") (pinfunction "V+_8") (pintype "power_in"))
      (node (ref "U9") (pin "2") (pinfunction "GND1_2") (pintype "power_in"))
      (node (ref "U9") (pin "8") (pinfunction "GND1_8") (pintype "power_in"))
    )
    (net (code "5") (name "Net-(C1-Pad1)") (class "Default")
      (node (ref "C1") (pin "1") (pinfunction "1_1") (pintype "passive"))
      (node (ref "R2") (pin "1") (pinfunction "1_1") (pintype "passive"))
    )
    (net (code "6") (name "Net-(C17-Pad1)") (class "Default")
      (node (ref "C17") (pin "1") (pinfunction "1_1") (pintype "passive"))
      (node (ref "R14") (pin "1") (pinfunction "1_1") (pintype "passive"))
    )
    (net (code "7") (name "Net-(C31-Pad1)") (class "Default")
      (node (ref "C31") (pin "1") (pinfunction "1_1") (pintype "passive"))
      (node (ref "R27") (pin "1") (pinfunction "1_1") (pintype "passive"))
    )
    (net (code "8") (name "Net-(D1-A)") (class "Default")
      (node (ref "C12") (pin "1") (pinfunction "1_1") (pintype "passive"))
      (node (ref "D1") (pin "1") (pinfunction "A_1") (pintype "passive"))
      (node (ref "P1") (pin "1") (pinfunction "1_1") (pintype "passive"))
      (node (ref "R7") (pin "2") (pinfunction "2_2") (pintype "passive"))
    )
    (net (code "9") (name "Net-(D2-A)") (class "Default")
      (node (ref "C26") (pin "1") (pinfunction "1_1") (pintype "passive"))
      (node (ref "D2") (pin "1") (pinfunction "A_1") (pintype "passive"))
      (node (ref "P1") (pin "2") (pinfunction "2_2") (pintype "passive"))
      (node (ref "R20") (pin "2") (pinfunction "2_2") (pintype "passive"))
    )
    (net (code "10") (name "Net-(D3-A)") (class "Default")
      (node (ref "C40") (pin "1") (pinfunction "1_1") (pintype "passive"))
      (node (ref "D3") (pin "1") (pinfunction "A_1") (pintype "passive"))
      (node (ref "P1") (pin "3") (pinfunction "3_3") (pintype "passive"))
      (node (ref "R32") (pin "2") (pinfunction "2_2") (pintype "passive"))
    )
    (net (code "11") (name "Net-(P1-Pad7)") (class "Default")
      (node (ref "P1") (pin "7") (pinfunction "7_7") (pintype "passive"))
      (node (ref "P5") (pin "4") (pinfunction "4_4") (pintype "passive"))
    )
    (net (code "12") (name "Net-(P1-Pad8)") (class "Default")
      (node (ref "P1") (pin "8") (pinfunction "8_8") (pintype "passive"))
      (node (ref "P5") (pin "3") (pinfunction "3_3") (pintype "passive"))
    )
    (net (code "13") (name "Net-(P4-Pad1)") (class "Default")
      (node (ref "P4") (pin "1") (pinfunction "1_1") (pintype "passive"))
      (node (ref "R19") (pin "1") (pinfunction "1_1") (pintype "passive"))
    )
    (net (code "14") (name "Net-(P4-Pad2)") (class "Default")
      (node (ref "P4") (pin "2") (pinfunction "2_2") (pintype "passive"))
      (node (ref "R16") (pin "1") (pinfunction "1_1") (pintype "passive"))
    )
    (net (code "15") (name "Net-(P4-Pad3)") (class "Default")
      (node (ref "P4") (pin "3") (pinfunction "3_3") (pintype "passive"))
      (node (ref "R13") (pin "1") (pinfunction "1_1") (pintype "passive"))
    )
    (net (code "16") (name "Net-(P4-Pad4)") (class "Default")
      (node (ref "P4") (pin "4") (pinfunction "4_4") (pintype "passive"))
      (node (ref "R10") (pin "1") (pinfunction "1_1") (pintype "passive"))
    )
    (net (code "17") (name "Net-(P4-Pad5)") (class "Default")
      (node (ref "P4") (pin "5") (pinfunction "5_5") (pintype "passive"))
      (node (ref "R6") (pin "1") (pinfunction "1_1") (pintype "passive"))
    )
    (net (code "18") (name "Net-(P4-Pad6)") (class "Default")
      (node (ref "P4") (pin "6") (pinfunction "6_6") (pintype "passive"))
      (node (ref "R3") (pin "1") (pinfunction "1_1") (pintype "passive"))
    )
    (net (code "19") (name "Net-(P4-Pad7)") (class "Default")
      (node (ref "P4") (pin "7") (pinfunction "7_7") (pintype "passive"))
      (node (ref "R23") (pin "1") (pinfunction "1_1") (pintype "passive"))
    )
    (net (code "20") (name "Net-(P4-Pad8)") (class "Default")
      (node (ref "P4") (pin "8") (pinfunction "8_8") (pintype "passive"))
      (node (ref "R26") (pin "1") (pinfunction "1_1") (pintype "passive"))
    )
    (net (code "21") (name "Net-(P4-Pad9)") (class "Default")
      (node (ref "P4") (pin "9") (pinfunction "9_9") (pintype "passive"))
      (node (ref "R29") (pin "1") (pinfunction "1_1") (pintype "passive"))
    )
    (net (code "22") (name "Net-(Q1-B)") (class "Default")
      (node (ref "Q1") (pin "2") (pinfunction "B_2") (pintype "passive"))
      (node (ref "R2") (pin "2") (pinfunction "2_2") (pintype "passive"))
    )
    (net (code "23") (name "Net-(Q1-E)") (class "Default")
      (node (ref "Q1") (pin "1") (pinfunction "E_1") (pintype "passive"))
      (node (ref "Q2") (pin "1") (pinfunction "LED_CATHODE_1") (pintype "passive"))
    )
    (net (code "24") (name "Net-(Q2-LED_ANODE)") (class "Default")
      (node (ref "Q2") (pin "2") (pinfunction "LED_ANODE_2") (pintype "passive"))
      (node (ref "R5") (pin "2") (pinfunction "2_2") (pintype "passive"))
    )
    (net (code "25") (name "Net-(Q2-PD1_CATHODE)") (class "Default")
      (node (ref "C1") (pin "2") (pinfunction "2_2") (pintype "passive"))
      (node (ref "C13") (pin "1") (pinfunction "1_1") (pintype "passive"))
      (node (ref "Q2") (pin "3") (pinfunction "PD1_CATHODE_3") (pintype "passive"))
      (node (ref "R9") (pin "2") (pinfunction "2_2") (pintype "passive"))
      (node (ref "U1") (pin "2") (pinfunction "INVERTING_INPUT_A_2") (pintype "tri_state"))
    )
    (net (code "26") (name "Net-(Q2-PD2_CATHODE)") (class "Default")
      (node (ref "C8") (pin "2") (pinfunction "2_2") (pintype "passive"))
      (node (ref "Q2") (pin "6") (pinfunction "PD2_CATHODE_6") (pintype "passive"))
      (node (ref "R1") (pin "1") (pinfunction "1_1") (pintype "passive"))
      (node (ref "U3") (pin "2") (pinfunction "INVERTING_INPUT_A_2") (pintype "tri_state"))
    )
    (net (code "27") (name "Net-(Q3-B)") (class "Default")
      (node (ref "Q3") (pin "2") (pinfunction "B_2") (pintype "passive"))
      (node (ref "R14") (pin "2") (pinfunction "2_2") (pintype "passive"))
    )
    (net (code "28") (name "Net-(Q3-E)") (class "Default")
      (node (ref "Q3") (pin "1") (pinfunction "E_1") (pintype "passive"))
      (node (ref "Q4") (pin "1") (pinfunction "LED_CATHODE_1") (pintype "passive"))
    )
    (net (code "29") (name "Net-(Q4-LED_ANODE)") (class "Default")
      (node (ref "Q4") (pin "2") (pinfunction "LED_ANODE_2") (pintype "passive"))
      (node (ref "R18") (pin "2") (pinfunction "2_2") (pintype "passive"))
    )
    (net (code "30") (name "Net-(Q4-PD1_CATHODE)") (class "Default")
      (node (ref "C17") (pin "2") (pinfunction "2_2") (pintype "passive"))
      (node (ref "C27") (pin "1") (pinfunction "1_1") (pintype "passive"))
      (node (ref "Q4") (pin "3") (pinfunction "PD1_CATHODE_3") (pintype "passive"))
      (node (ref "R21") (pin "2") (pinfunction "2_2") (pintype "passive"))
      (node (ref "U5") (pin "2") (pinfunction "INVERTING_INPUT_A_2") (pintype "tri_state"))
    )
    (net (code "31") (name "Net-(Q4-PD2_CATHODE)") (class "Default")
      (node (ref "C21") (pin "2") (pinfunction "2_2") (pintype "passive"))
      (node (ref "Q4") (pin "6") (pinfunction "PD2_CATHODE_6") (pintype "passive"))
      (node (ref "R12") (pin "1") (pinfunction "1_1") (pintype "passive"))
      (node (ref "U7") (pin "2") (pinfunction "INVERTING_INPUT_A_2") (pintype "tri_state"))
    )
    (net (code "32") (name "Net-(Q5-B)") (class "Default")
      (node (ref "Q5") (pin "2") (pinfunction "B_2") (pintype "passive"))
      (node (ref "R27") (pin "2") (pinfunction "2_2") (pintype "passive"))
    )
    (net (code "33") (name "Net-(Q5-E)") (class "Default")
      (node (ref "Q5") (pin "1") (pinfunction "E_1") (pintype "passive"))
      (node (ref "Q6") (pin "1") (pinfunction "LED_CATHODE_1") (pintype "passive"))
    )
    (net (code "34") (name "Net-(Q6-LED_ANODE)") (class "Default")
      (node (ref "Q6") (pin "2") (pinfunction "LED_ANODE_2") (pintype "passive"))
      (node (ref "R31") (pin "2") (pinfunction "2_2") (pintype "passive"))
    )
    (net (code "35") (name "Net-(Q6-PD1_CATHODE)") (class "Default")
      (node (ref "C31") (pin "2") (pinfunction "2_2") (pintype "passive"))
      (node (ref "C41") (pin "1") (pinfunction "1_1") (pintype "passive"))
      (node (ref "Q6") (pin "3") (pinfunction "PD1_CATHODE_3") (pintype "passive"))
      (node (ref "R33") (pin "2") (pinfunction "2_2") (pintype "passive"))
      (node (ref "U10") (pin "2") (pinfunction "INVERTING_INPUT_A_2") (pintype "tri_state"))
    )
    (net (code "36") (name "Net-(Q6-PD2_CATHODE)") (class "Default")
      (node (ref "C36") (pin "2") (pinfunction "2_2") (pintype "passive"))
      (node (ref "Q6") (pin "6") (pinfunction "PD2_CATHODE_6") (pintype "passive"))
      (node (ref "R24") (pin "1") (pinfunction "1_1") (pintype "passive"))
      (node (ref "U11") (pin "2") (pinfunction "INVERTING_INPUT_A_2") (pintype "tri_state"))
    )
    (net (code "37") (name "Net-(U2A-A1)") (class "Default")
      (node (ref "R3") (pin "2") (pinfunction "2_2") (pintype "passive"))
      (node (ref "R4") (pin "1") (pinfunction "1_1") (pintype "passive"))
      (node (ref "U2") (pin "3") (pinfunction "A1_3") (pintype "input"))
    )
    (net (code "38") (name "Net-(U2A-A2)") (class "Default")
      (node (ref "R6") (pin "2") (pinfunction "2_2") (pintype "passive"))
      (node (ref "R8") (pin "1") (pinfunction "1_1") (pintype "passive"))
      (node (ref "U2") (pin "4") (pinfunction "A2_4") (pintype "input"))
    )
    (net (code "39") (name "Net-(U2A-A3)") (class "Default")
      (node (ref "R10") (pin "2") (pinfunction "2_2") (pintype "passive"))
      (node (ref "R11") (pin "1") (pinfunction "1_1") (pintype "passive"))
      (node (ref "U2") (pin "5") (pinfunction "A3_5") (pintype "input"))
    )
    (net (code "40") (name "Net-(U2A-B1)") (class "Default")
      (node (ref "P3") (pin "1") (pinfunction "1_1") (pintype "passive"))
      (node (ref "U2") (pin "14") (pinfunction "B1_14") (pintype "output"))
    )
    (net (code "41") (name "Net-(U2A-B2)") (class "Default")
      (node (ref "P3") (pin "2") (pinfunction "2_2") (pintype "passive"))
      (node (ref "U2") (pin "13") (pinfunction "B2_13") (pintype "output"))
    )
    (net (code "42") (name "Net-(U2A-B3)") (class "Default")
      (node (ref "P3") (pin "3") (pinfunction "3_3") (pintype "passive"))
      (node (ref "U2") (pin "12") (pinfunction "B3_12") (pintype "output"))
    )
    (net (code "43") (name "Net-(U3A-OUTPUT_A)") (class "Default")
      (node (ref "C8") (pin "1") (pinfunction "1_1") (pintype "passive"))
      (node (ref "R1") (pin "2") (pinfunction "2_2") (pintype "passive"))
      (node (ref "R7") (pin "1") (pinfunction "1_1") (pintype "passive"))
      (node (ref "U3") (pin "1") (pinfunction "OUTPUT_A_1") (pintype "output"))
    )
    (net (code "44") (name "Net-(U4A-INVERTING_INPUT_A)") (class "Default")
      (node (ref "R9") (pin "1") (pinfunction "1_1") (pintype "passive"))
      (node (ref "U4") (pin "1") (pinfunction "OUTPUT_A_1") (pintype "output"))
      (node (ref "U4") (pin "2") (pinfunction "INVERTING_INPUT_A_2") (pintype "tri_state"))
    )
    (net (code "45") (name "Net-(U4A-NON-INVERTING_INPUT_A)") (class "Default")
      (node (ref "C14") (pin "1") (pinfunction "1_1") (pintype "passive"))
      (node (ref "P2") (pin "8") (pinfunction "8_8") (pintype "passive"))
      (node (ref "U4") (pin "3") (pinfunction "NON-INVERTING_INPUT_A_3") (pintype "tri_state"))
    )
    (net (code "46") (name "Net-(U6A-A1)") (class "Default")
      (node (ref "R13") (pin "2") (pinfunction "2_2") (pintype "passive"))
      (node (ref "R15") (pin "1") (pinfunction "1_1") (pintype "passive"))
      (node (ref "U6") (pin "3") (pinfunction "A1_3") (pintype "input"))
    )
    (net (code "47") (name "Net-(U6A-A2)") (class "Default")
      (node (ref "R16") (pin "2") (pinfunction "2_2") (pintype "passive"))
      (node (ref "R17") (pin "1") (pinfunction "1_1") (pintype "passive"))
      (node (ref "U6") (pin "4") (pinfunction "A2_4") (pintype "input"))
    )
    (net (code "48") (name "Net-(U6A-A3)") (class "Default")
      (node (ref "R19") (pin "2") (pinfunction "2_2") (pintype "passive"))
      (node (ref "R22") (pin "1") (pinfunction "1_1") (pintype "passive"))
      (node (ref "U6") (pin "5") (pinfunction "A3_5") (pintype "input"))
    )
    (net (code "49") (name "Net-(U6A-B1)") (class "Default")
      (node (ref "P3") (pin "4") (pinfunction "4_4") (pintype "passive"))
      (node (ref "U6") (pin "14") (pinfunction "B1_14") (pintype "output"))
    )
    (net (code "50") (name "Net-(U6A-B2)") (class "Default")
      (node (ref "P3") (pin "5") (pinfunction "5_5") (pintype "passive"))
      (node (ref "U6") (pin "13") (pinfunction "B2_13") (pintype "output"))
    )
    (net (code "51") (name "Net-(U6A-B3)") (class "Default")
      (node (ref "P3") (pin "6") (pinfunction "6_6") (pintype "passive"))
      (node (ref "U6") (pin "12") (pinfunction "B3_12") (pintype "output"))
    )
    (net (code "52") (name "Net-(U7A-OUTPUT_A)") (class "Default")
      (node (ref "C21") (pin "1") (pinfunction "1_1") (pintype "passive"))
      (node (ref "R12") (pin "2") (pinfunction "2_2") (pintype "passive"))
      (node (ref "R20") (pin "1") (pinfunction "1_1") (pintype "passive"))
      (node (ref "U7") (pin "1") (pinfunction "OUTPUT_A_1") (pintype "output"))
    )
    (net (code "53") (name "Net-(U8A-INVERTING_INPUT_A)") (class "Default")
      (node (ref "R21") (pin "1") (pinfunction "1_1") (pintype "passive"))
      (node (ref "U8") (pin "1") (pinfunction "OUTPUT_A_1") (pintype "output"))
      (node (ref "U8") (pin "2") (pinfunction "INVERTING_INPUT_A_2") (pintype "tri_state"))
    )
    (net (code "54") (name "Net-(U8A-NON-INVERTING_INPUT_A)") (class "Default")
      (node (ref "C28") (pin "1") (pinfunction "1_1") (pintype "passive"))
      (node (ref "P2") (pin "7") (pinfunction "7_7") (pintype "passive"))
      (node (ref "U8") (pin "3") (pinfunction "NON-INVERTING_INPUT_A_3") (pintype "tri_state"))
    )
    (net (code "55") (name "Net-(U9A-A1)") (class "Default")
      (node (ref "R23") (pin "2") (pinfunction "2_2") (pintype "passive"))
      (node (ref "R25") (pin "1") (pinfunction "1_1") (pintype "passive"))
      (node (ref "U9") (pin "3") (pinfunction "A1_3") (pintype "input"))
    )
    (net (code "56") (name "Net-(U9A-A2)") (class "Default")
      (node (ref "R26") (pin "2") (pinfunction "2_2") (pintype "passive"))
      (node (ref "R28") (pin "1") (pinfunction "1_1") (pintype "passive"))
      (node (ref "U9") (pin "4") (pinfunction "A2_4") (pintype "input"))
    )
    (net (code "57") (name "Net-(U9A-A3)") (class "Default")
      (node (ref "R29") (pin "2") (pinfunction "2_2") (pintype "passive"))
      (node (ref "R30") (pin "1") (pinfunction "1_1") (pintype "passive"))
      (node (ref "U9") (pin "5") (pinfunction "A3_5") (pintype "input"))
    )
    (net (code "58") (name "Net-(U9A-B1)") (class "Default")
      (node (ref "P3") (pin "11") (pinfunction "11_11") (pintype "passive"))
      (node (ref "U9") (pin "14") (pinfunction "B1_14") (pintype "output"))
    )
    (net (code "59") (name "Net-(U9A-B2)") (class "Default")
      (node (ref "P3") (pin "10") (pinfunction "10_10") (pintype "passive"))
      (node (ref "U9") (pin "13") (pinfunction "B2_13") (pintype "output"))
    )
    (net (code "60") (name "Net-(U9A-B3)") (class "Default")
      (node (ref "P3") (pin "9") (pinfunction "9_9") (pintype "passive"))
      (node (ref "U9") (pin "12") (pinfunction "B3_12") (pintype "output"))
    )
    (net (code "61") (name "Net-(U11A-OUTPUT_A)") (class "Default")
      (node (ref "C36") (pin "1") (pinfunction "1_1") (pintype "passive"))
      (node (ref "R24") (pin "2") (pinfunction "2_2") (pintype "passive"))
      (node (ref "R32") (pin "1") (pinfunction "1_1") (pintype "passive"))
      (node (ref "U11") (pin "1") (pinfunction "OUTPUT_A_1") (pintype "output"))
    )
    (net (code "62") (name "Net-(U12A-INVERTING_INPUT_A)") (class "Default")
      (node (ref "R33") (pin "1") (pinfunction "1_1") (pintype "passive"))
      (node (ref "U12") (pin "1") (pinfunction "OUTPUT_A_1") (pintype "output"))
      (node (ref "U12") (pin "2") (pinfunction "INVERTING_INPUT_A_2") (pintype "tri_state"))
    )
    (net (code "63") (name "Net-(U12A-NON-INVERTING_INPUT_A)") (class "Default")
      (node (ref "C42") (pin "1") (pinfunction "1_1") (pintype "passive"))
      (node (ref "P2") (pin "6") (pinfunction "6_6") (pintype "passive"))
      (node (ref "U12") (pin "3") (pinfunction "NON-INVERTING_INPUT_A_3") (pintype "tri_state"))
    )
    (net (code "64") (name "PGND") (class "Default")
      (node (ref "C10") (pin "1") (pinfunction "C_1") (pintype "passive"))
      (node (ref "C11") (pin "2") (pinfunction "2_2") (pintype "passive"))
      (node (ref "C13") (pin "2") (pinfunction "2_2") (pintype "passive"))
      (node (ref "C14") (pin "2") (pinfunction "2_2") (pintype "passive"))
      (node (ref "C18") (pin "2") (pinfunction "2_2") (pintype "passive"))
      (node (ref "C19") (pin "1") (pinfunction "C_1") (pintype "passive"))
      (node (ref "C2") (pin "2") (pinfunction "2_2") (pintype "passive"))
      (node (ref "C20") (pin "2") (pinfunction "2_2") (pintype "passive"))
      (node (ref "C22") (pin "1") (pinfunction "C_1") (pintype "passive"))
      (node (ref "C23") (pin "2") (pinfunction "2_2") (pintype "passive"))
      (node (ref "C27") (pin "2") (pinfunction "2_2") (pintype "passive"))
      (node (ref "C28") (pin "2") (pinfunction "2_2") (pintype "passive"))
      (node (ref "C29") (pin "2") (pinfunction "2_2") (pintype "passive"))
      (node (ref "C30") (pin "1") (pinfunction "C_1") (pintype "passive"))
      (node (ref "C34") (pin "2") (pinfunction "2_2") (pintype "passive"))
      (node (ref "C35") (pin "1") (pinfunction "C_1") (pintype "passive"))
      (node (ref "C39") (pin "2") (pinfunction "2_2") (pintype "passive"))
      (node (ref "C41") (pin "2") (pinfunction "2_2") (pintype "passive"))
      (node (ref "C42") (pin "2") (pinfunction "2_2") (pintype "passive"))
      (node (ref "C5") (pin "1") (pinfunction "C_1") (pintype "passive"))
      (node (ref "C9") (pin "2") (pinfunction "2_2") (pintype "passive"))
      (node (ref "P2") (pin "1") (pinfunction "1_1") (pintype "passive"))
      (node (ref "P3") (pin "7") (pinfunction "7_7") (pintype "passive"))
      (node (ref "Q1") (pin "3") (pinfunction "C_3") (pintype "passive"))
      (node (ref "Q2") (pin "4") (pinfunction "PD1_ANODE_4") (pintype "passive"))
      (node (ref "Q3") (pin "3") (pinfunction "C_3") (pintype "passive"))
      (node (ref "Q4") (pin "4") (pinfunction "PD1_ANODE_4") (pintype "passive"))
      (node (ref "Q5") (pin "3") (pinfunction "C_3") (pintype "passive"))
      (node (ref "Q6") (pin "4") (pinfunction "PD1_ANODE_4") (pintype "passive"))
      (node (ref "U1") (pin "3") (pinfunction "NON-INVERTING_INPUT_A_3") (pintype "tri_state"))
      (node (ref "U1") (pin "8") (pinfunction "V+_8") (pintype "power_in"))
      (node (ref "U10") (pin "3") (pinfunction "NON-INVERTING_INPUT_A_3") (pintype "tri_state"))
      (node (ref "U10") (pin "8") (pinfunction "V+_8") (pintype "power_in"))
      (node (ref "U12") (pin "8") (pinfunction "V+_8") (pintype "power_in"))
      (node (ref "U2") (pin "15") (pinfunction "GND2_15") (pintype "power_in"))
      (node (ref "U2") (pin "9") (pinfunction "GND2_9") (pintype "power_in"))
      (node (ref "U4") (pin "8") (pinfunction "V+_8") (pintype "power_in"))
      (node (ref "U5") (pin "3") (pinfunction "NON-INVERTING_INPUT_A_3") (pintype "tri_state"))
      (node (ref "U5") (pin "8") (pinfunction "V+_8") (pintype "power_in"))
      (node (ref "U6") (pin "15") (pinfunction "GND2_15") (pintype "power_in"))
      (node (ref "U6") (pin "9") (pinfunction "GND2_9") (pintype "power_in"))
      (node (ref "U8") (pin "8") (pinfunction "V+_8") (pintype "power_in"))
      (node (ref "U9") (pin "15") (pinfunction "GND2_15") (pintype "power_in"))
      (node (ref "U9") (pin "9") (pinfunction "GND2_9") (pintype "power_in"))
    )
    (net (code "65") (name "iso 15") (class "Default")
      (node (ref "C10") (pin "2") (pinfunction "A_2") (pintype "passive"))
      (node (ref "C11") (pin "1") (pinfunction "1_1") (pintype "passive"))
      (node (ref "C20") (pin "1") (pinfunction "1_1") (pintype "passive"))
      (node (ref "C22") (pin "2") (pinfunction "A_2") (pintype "passive"))
      (node (ref "C23") (pin "1") (pinfunction "1_1") (pintype "passive"))
      (node (ref "C34") (pin "1") (pinfunction "1_1") (pintype "passive"))
      (node (ref "C35") (pin "2") (pinfunction "A_2") (pintype "passive"))
      (node (ref "C39") (pin "1") (pinfunction "1_1") (pintype "passive"))
      (node (ref "C9") (pin "1") (pinfunction "1_1") (pintype "passive"))
      (node (ref "P2") (pin "2") (pinfunction "2_2") (pintype "passive"))
      (node (ref "R18") (pin "1") (pinfunction "1_1") (pintype "passive"))
      (node (ref "R31") (pin "1") (pinfunction "1_1") (pintype "passive"))
      (node (ref "R5") (pin "1") (pinfunction "1_1") (pintype "passive"))
      (node (ref "U1") (pin "4") (pinfunction "GND_4") (pintype "power_in"))
      (node (ref "U10") (pin "4") (pinfunction "GND_4") (pintype "power_in"))
      (node (ref "U12") (pin "4") (pinfunction "GND_4") (pintype "power_in"))
      (node (ref "U4") (pin "4") (pinfunction "GND_4") (pintype "power_in"))
      (node (ref "U5") (pin "4") (pinfunction "GND_4") (pintype "power_in"))
      (node (ref "U8") (pin "4") (pinfunction "GND_4") (pintype "power_in"))
    )
    (net (code "66") (name "iso-5V0") (class "Default")
      (node (ref "C18") (pin "1") (pinfunction "1_1") (pintype "passive"))
      (node (ref "C19") (pin "2") (pinfunction "A_2") (pintype "passive"))
      (node (ref "C2") (pin "1") (pinfunction "1_1") (pintype "passive"))
      (node (ref "C29") (pin "1") (pinfunction "1_1") (pintype "passive"))
      (node (ref "C30") (pin "2") (pinfunction "A_2") (pintype "passive"))
      (node (ref "C5") (pin "2") (pinfunction "A_2") (pintype "passive"))
      (node (ref "P3") (pin "8") (pinfunction "8_8") (pintype "passive"))
      (node (ref "U2") (pin "16") (pinfunction "VDD2_16") (pintype "power_in"))
      (node (ref "U6") (pin "16") (pinfunction "VDD2_16") (pintype "power_in"))
      (node (ref "U9") (pin "16") (pinfunction "VDD2_16") (pintype "power_in"))
    )
    (net (code "67") (name "unconnected-(P2-Pad3)") (class "Default")
      (node (ref "P2") (pin "3") (pinfunction "3_3") (pintype "passive"))
    )
    (net (code "68") (name "unconnected-(P2-Pad4)") (class "Default")
      (node (ref "P2") (pin "4") (pinfunction "4_4") (pintype "passive"))
    )
    (net (code "69") (name "unconnected-(P2-Pad5)") (class "Default")
      (node (ref "P2") (pin "5") (pinfunction "5_5") (pintype "passive"))
    )
    (net (code "70") (name "unconnected-(P3-Pad12)") (class "Default")
      (node (ref "P3") (pin "12") (pinfunction "12_12") (pintype "passive"))
    )
    (net (code "71") (name "unconnected-(P4-Pad10)") (class "Default")
      (node (ref "P4") (pin "10") (pinfunction "10_10") (pintype "passive"))
    )
    (net (code "72") (name "unconnected-(P4-Pad11)") (class "Default")
      (node (ref "P4") (pin "11") (pinfunction "11_11") (pintype "passive"))
    )
    (net (code "73") (name "unconnected-(P5-Pad2)") (class "Default")
      (node (ref "P5") (pin "2") (pinfunction "2_2") (pintype "passive"))
    )
    (net (code "74") (name "unconnected-(Q2-NC-Pad7)") (class "Default")
      (node (ref "Q2") (pin "7") (pinfunction "NC_7") (pintype "passive+no_connect"))
    )
    (net (code "75") (name "unconnected-(Q2-NC-Pad8)") (class "Default")
      (node (ref "Q2") (pin "8") (pinfunction "NC_8") (pintype "passive+no_connect"))
    )
    (net (code "76") (name "unconnected-(Q4-NC-Pad7)") (class "Default")
      (node (ref "Q4") (pin "7") (pinfunction "NC_7") (pintype "passive+no_connect"))
    )
    (net (code "77") (name "unconnected-(Q4-NC-Pad8)") (class "Default")
      (node (ref "Q4") (pin "8") (pinfunction "NC_8") (pintype "passive+no_connect"))
    )
    (net (code "78") (name "unconnected-(Q6-NC-Pad7)") (class "Default")
      (node (ref "Q6") (pin "7") (pinfunction "NC_7") (pintype "passive+no_connect"))
    )
    (net (code "79") (name "unconnected-(Q6-NC-Pad8)") (class "Default")
      (node (ref "Q6") (pin "8") (pinfunction "NC_8") (pintype "passive+no_connect"))
    )
    (net (code "80") (name "unconnected-(U1A-OUTPUT_A-Pad1)") (class "Default")
      (node (ref "U1") (pin "1") (pinfunction "OUTPUT_A_1") (pintype "output"))
    )
    (net (code "81") (name "unconnected-(U5A-OUTPUT_A-Pad1)") (class "Default")
      (node (ref "U5") (pin "1") (pinfunction "OUTPUT_A_1") (pintype "output"))
    )
    (net (code "82") (name "unconnected-(U10A-OUTPUT_A-Pad1)") (class "Default")
      (node (ref "U10") (pin "1") (pinfunction "OUTPUT_A_1") (pintype "output"))
    )
  )
)
